# VoltageSourcePCB.net
KiCad netlist of a schematic drawn in EAGLE
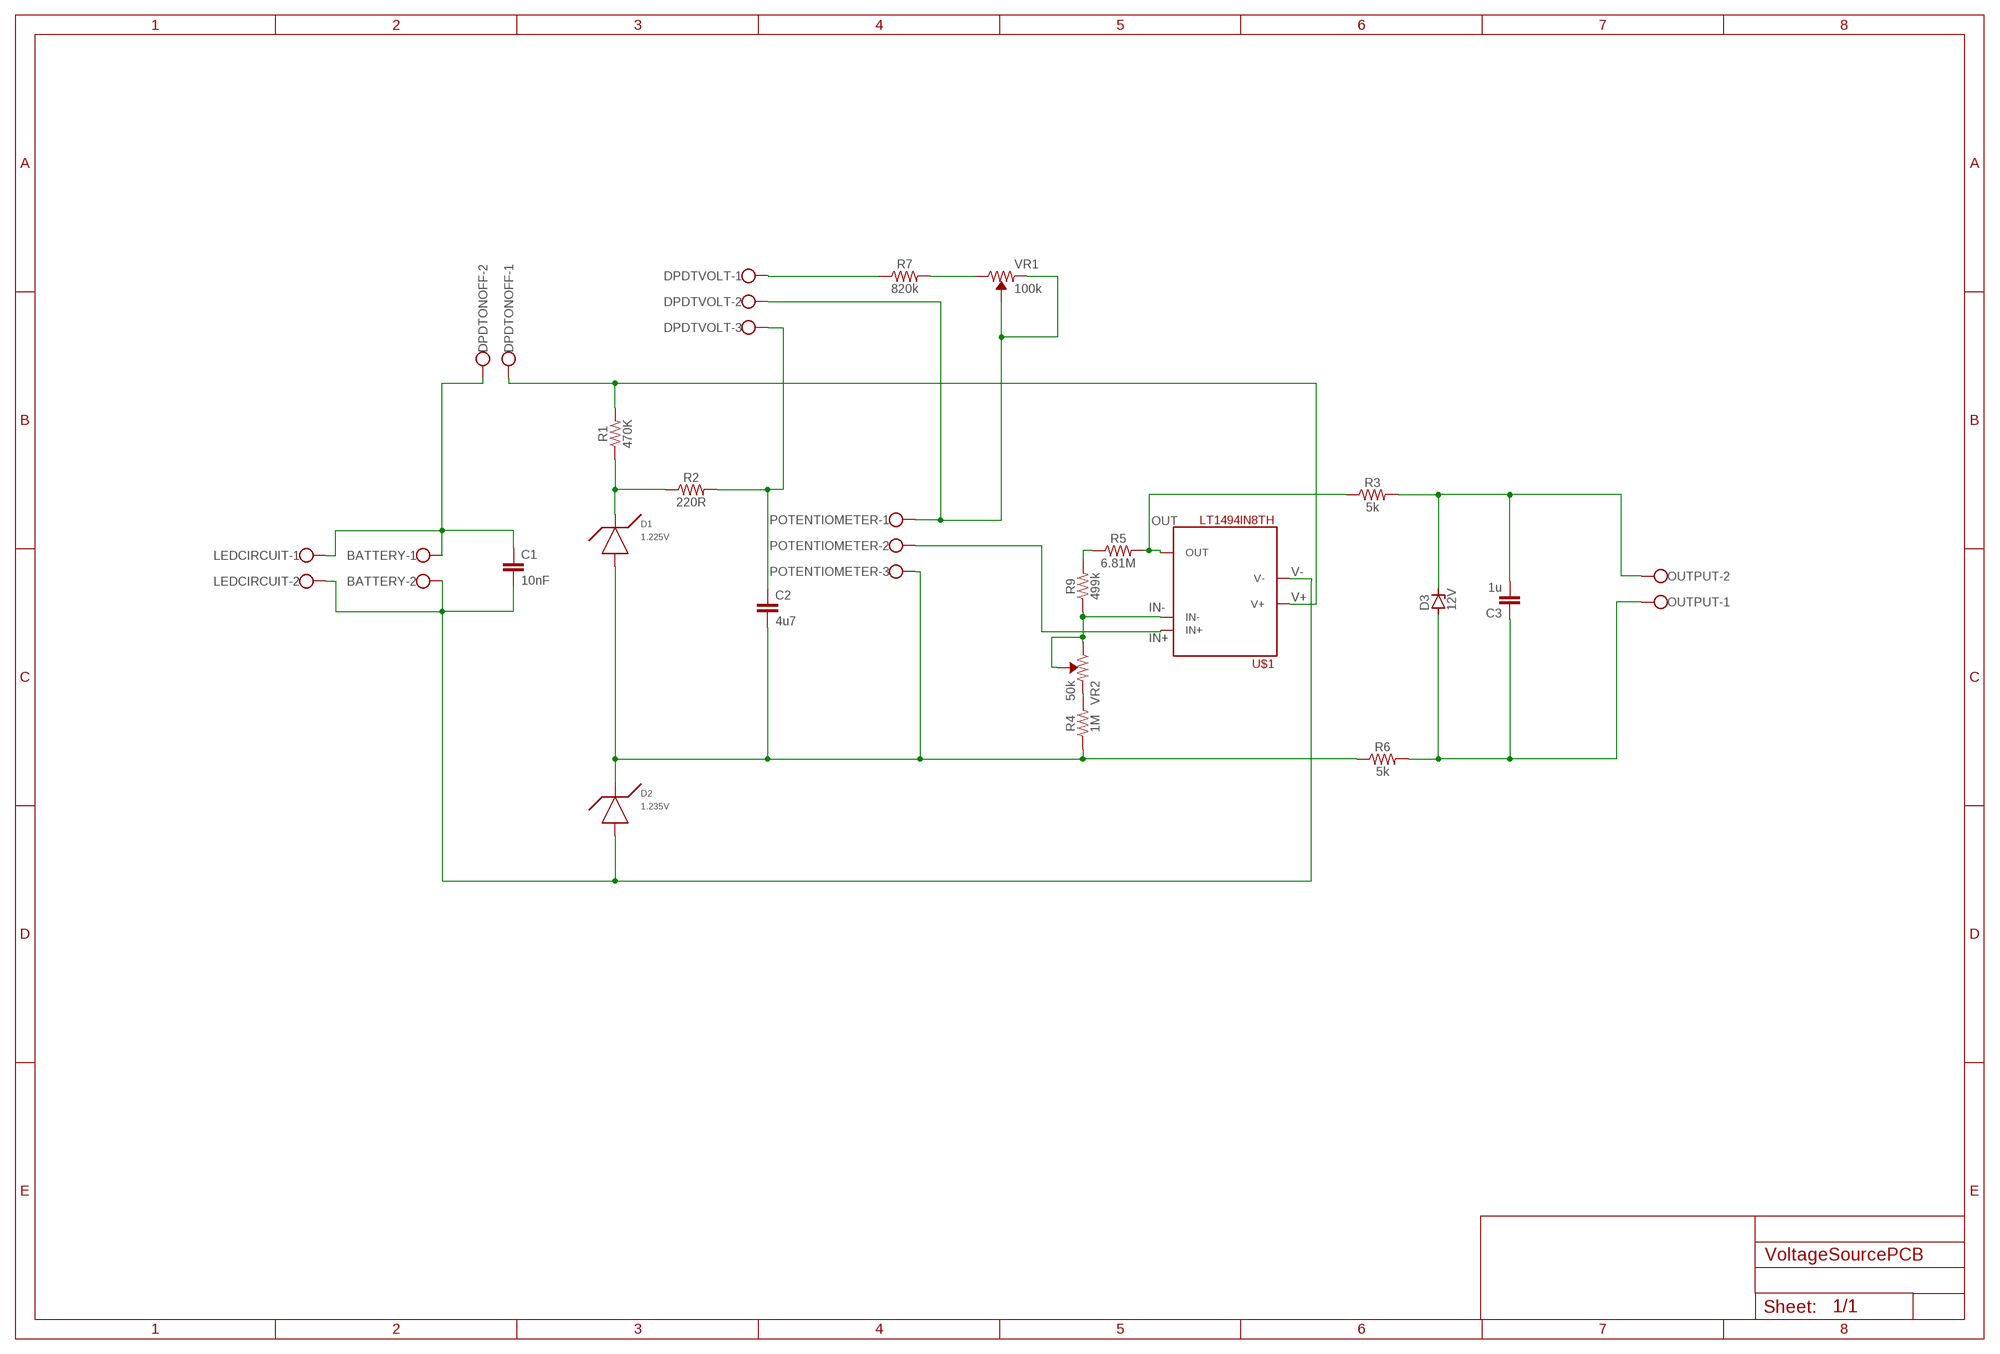
[diagram p0: schematic, sheet 1]

(export (version "E")
  (design (tool "Eeschema 10.0.6"))
  (components
    (comp (ref "BATTERY")
      (value "W237-102")
      (footprint "eagle-import:W237-102")
      (fields (field (name "MPN") "237-102"))
      (libsource (lib "eagle-import") (part "W237-102"))
    )
    (comp (ref "C1")
      (value "10nF")
      (footprint "eagle-import:C5B2.5")
      (libsource (lib "eagle-import") (part "C5/2.5"))
    )
    (comp (ref "C2")
      (value "4u7")
      (footprint "eagle-import:C22.5B11")
      (libsource (lib "eagle-import") (part "C22/11"))
    )
    (comp (ref "C3")
      (value "1u")
      (footprint "eagle-import:C150-072X183")
      (libsource (lib "eagle-import") (part "C-EU150-072X183"))
    )
    (comp (ref "D1")
      (value "1.225V")
      (footprint "eagle-import:LT1004CZ")
      (libsource (lib "eagle-import") (part "LT1004CZ1.225V"))
    )
    (comp (ref "D2")
      (value "1.235V")
      (footprint "eagle-import:LT1004CZ")
      (libsource (lib "eagle-import") (part "LT1004CZ1.235V"))
    )
    (comp (ref "D3")
      (value "12V")
      (footprint "eagle-import:C1702-15")
      (libsource (lib "eagle-import") (part "ZENER-DIODEC1702-15"))
    )
    (comp (ref "DPDTONOFF")
      (value "W237-102")
      (footprint "eagle-import:W237-102")
      (fields (field (name "MPN") "237-102"))
      (libsource (lib "eagle-import") (part "W237-102"))
    )
    (comp (ref "DPDTVOLT")
      (value "W237-103")
      (footprint "eagle-import:W237-103")
      (fields (field (name "MPN") "237-103"))
      (libsource (lib "eagle-import") (part "W237-103"))
    )
    (comp (ref "LEDCIRCUIT")
      (value "W237-102")
      (footprint "eagle-import:W237-102")
      (fields (field (name "MPN") "237-102"))
      (libsource (lib "eagle-import") (part "W237-102"))
    )
    (comp (ref "OUTPUT")
      (value "W237-102")
      (footprint "eagle-import:W237-102")
      (fields (field (name "MPN") "237-102"))
      (libsource (lib "eagle-import") (part "W237-102"))
    )
    (comp (ref "POTENTIOMETER")
      (value "W237-103")
      (footprint "eagle-import:W237-103")
      (fields (field (name "MPN") "237-103"))
      (libsource (lib "eagle-import") (part "W237-103"))
    )
    (comp (ref "R1")
      (value "470K")
      (footprint "eagle-import:0805")
      (libsource (lib "eagle-import") (part "RESISTOR0805"))
    )
    (comp (ref "R2")
      (value "220R")
      (footprint "eagle-import:0805")
      (libsource (lib "eagle-import") (part "RESISTOR0805"))
    )
    (comp (ref "R3")
      (value "5k")
      (footprint "eagle-import:0805")
      (libsource (lib "eagle-import") (part "RESISTOR0805"))
    )
    (comp (ref "R4")
      (value "1M")
      (footprint "eagle-import:0805")
      (libsource (lib "eagle-import") (part "RESISTOR0805"))
    )
    (comp (ref "R5")
      (value "6.81M")
      (footprint "eagle-import:0805")
      (libsource (lib "eagle-import") (part "RESISTOR0805"))
    )
    (comp (ref "R6")
      (value "5k")
      (footprint "eagle-import:0805")
      (libsource (lib "eagle-import") (part "RESISTOR0805"))
    )
    (comp (ref "R7")
      (value "820k")
      (footprint "eagle-import:0805")
      (libsource (lib "eagle-import") (part "RESISTOR0805"))
    )
    (comp (ref "R9")
      (value "499k")
      (footprint "eagle-import:0805")
      (libsource (lib "eagle-import") (part "RESISTOR0805"))
    )
    (comp (ref "U$1")
      (value "LT1494IN8TH")
      (footprint "eagle-import:LT1494TH")
      (libsource (lib "eagle-import") (part "LT1494IN8TH"))
    )
    (comp (ref "VR1")
      (value "100k")
      (footprint "eagle-import:TRIMPOT-SMD-TC33X")
      (libsource (lib "eagle-import") (part "TRIMPOT-SMD-3MM-OPEN-1/10W-25%"))
    )
    (comp (ref "VR2")
      (value "50k")
      (footprint "eagle-import:TRIMPOT-SMD-TC33X")
      (libsource (lib "eagle-import") (part "TRIMPOT-SMD-3MM-OPEN-1/10W-25%"))
    )
  )
  (nets
    (net (code "1") (name "/IN+") (class "Default")
      (node (ref "POTENTIOMETER") (pin "2") (pinfunction "KL_2") (pintype "passive"))
      (node (ref "U$1") (pin "3") (pinfunction "IN+_3") (pintype "input"))
    )
    (net (code "2") (name "/IN-") (class "Default")
      (node (ref "R9") (pin "1") (pinfunction "1_1") (pintype "passive"))
      (node (ref "U$1") (pin "2") (pinfunction "IN-_2") (pintype "input"))
      (node (ref "VR2") (pin "1") (pinfunction "CW_1") (pintype "passive"))
      (node (ref "VR2") (pin "2") (pinfunction "WIPER_2") (pintype "passive"))
    )
    (net (code "3") (name "/OUT") (class "Default")
      (node (ref "R3") (pin "1") (pinfunction "1_1") (pintype "passive"))
      (node (ref "R5") (pin "2") (pinfunction "2_2") (pintype "passive"))
      (node (ref "U$1") (pin "6") (pinfunction "OUT_6") (pintype "output"))
    )
    (net (code "4") (name "/V+") (class "Default")
      (node (ref "DPDTONOFF") (pin "1") (pinfunction "KL_1") (pintype "passive"))
      (node (ref "R1") (pin "2") (pinfunction "2_2") (pintype "passive"))
      (node (ref "U$1") (pin "7") (pinfunction "V+_7") (pintype "power_in"))
    )
    (net (code "5") (name "/V-") (class "Default")
      (node (ref "BATTERY") (pin "2") (pinfunction "KL_2") (pintype "passive"))
      (node (ref "C1") (pin "2") (pinfunction "2_2") (pintype "passive"))
      (node (ref "D2") (pin "ANODE") (pinfunction "ANODE_ANODE") (pintype "bidirectional"))
      (node (ref "LEDCIRCUIT") (pin "2") (pinfunction "KL_2") (pintype "passive"))
      (node (ref "U$1") (pin "4") (pinfunction "V-_4") (pintype "power_in"))
    )
    (net (code "6") (name "Net-(BATTERYA-KL)") (class "Default")
      (node (ref "BATTERY") (pin "1") (pinfunction "KL_1") (pintype "passive"))
      (node (ref "C1") (pin "1") (pinfunction "1_1") (pintype "passive"))
      (node (ref "DPDTONOFF") (pin "2") (pinfunction "KL_2") (pintype "passive"))
      (node (ref "LEDCIRCUIT") (pin "1") (pinfunction "KL_1") (pintype "passive"))
    )
    (net (code "7") (name "Net-(D1-PadCATHODE)") (class "Default")
      (node (ref "D1") (pin "CATHODE") (pinfunction "CATHODE_CATHODE") (pintype "bidirectional"))
      (node (ref "R1") (pin "1") (pinfunction "1_1") (pintype "passive"))
      (node (ref "R2") (pin "1") (pinfunction "1_1") (pintype "passive"))
    )
    (net (code "8") (name "Net-(DPDTVOLTA-KL)") (class "Default")
      (node (ref "DPDTVOLT") (pin "1") (pinfunction "KL_1") (pintype "passive"))
      (node (ref "R7") (pin "1") (pinfunction "1_1") (pintype "passive"))
    )
    (net (code "9") (name "Net-(DPDTVOLTB-KL)") (class "Default")
      (node (ref "DPDTVOLT") (pin "2") (pinfunction "KL_2") (pintype "passive"))
      (node (ref "POTENTIOMETER") (pin "1") (pinfunction "KL_1") (pintype "passive"))
      (node (ref "VR1") (pin "2") (pinfunction "WIPER_2") (pintype "passive"))
      (node (ref "VR1") (pin "3") (pinfunction "CCW_3") (pintype "passive"))
    )
    (net (code "10") (name "Net-(DPDTVOLTC-KL)") (class "Default")
      (node (ref "C2") (pin "1") (pinfunction "1_1") (pintype "passive"))
      (node (ref "DPDTVOLT") (pin "3") (pinfunction "KL_3") (pintype "passive"))
      (node (ref "R2") (pin "2") (pinfunction "2_2") (pintype "passive"))
    )
    (net (code "11") (name "Net-(OUTPUTA-KL)") (class "Default")
      (node (ref "C3") (pin "1") (pinfunction "1_1") (pintype "passive"))
      (node (ref "D3") (pin "A") (pinfunction "A_A") (pintype "passive"))
      (node (ref "OUTPUT") (pin "1") (pinfunction "KL_1") (pintype "passive"))
      (node (ref "R6") (pin "2") (pinfunction "2_2") (pintype "passive"))
    )
    (net (code "12") (name "Net-(OUTPUTB-KL)") (class "Default")
      (node (ref "C3") (pin "2") (pinfunction "2_2") (pintype "passive"))
      (node (ref "D3") (pin "C") (pinfunction "C_C") (pintype "passive"))
      (node (ref "OUTPUT") (pin "2") (pinfunction "KL_2") (pintype "passive"))
      (node (ref "R3") (pin "2") (pinfunction "2_2") (pintype "passive"))
    )
    (net (code "13") (name "Net-(POTENTIOMETERC-KL)") (class "Default")
      (node (ref "C2") (pin "2") (pinfunction "2_2") (pintype "passive"))
      (node (ref "D1") (pin "ANODE") (pinfunction "ANODE_ANODE") (pintype "bidirectional"))
      (node (ref "D2") (pin "CATHODE") (pinfunction "CATHODE_CATHODE") (pintype "bidirectional"))
      (node (ref "POTENTIOMETER") (pin "3") (pinfunction "KL_3") (pintype "passive"))
      (node (ref "R4") (pin "1") (pinfunction "1_1") (pintype "passive"))
      (node (ref "R6") (pin "1") (pinfunction "1_1") (pintype "passive"))
    )
    (net (code "14") (name "Net-(R5-Pad1)") (class "Default")
      (node (ref "R5") (pin "1") (pinfunction "1_1") (pintype "passive"))
      (node (ref "R9") (pin "2") (pinfunction "2_2") (pintype "passive"))
    )
    (net (code "15") (name "Net-(VR1-CW)") (class "Default")
      (node (ref "R7") (pin "2") (pinfunction "2_2") (pintype "passive"))
      (node (ref "VR1") (pin "1") (pinfunction "CW_1") (pintype "passive"))
    )
    (net (code "16") (name "Net-(VR2-CCW)") (class "Default")
      (node (ref "R4") (pin "2") (pinfunction "2_2") (pintype "passive"))
      (node (ref "VR2") (pin "3") (pinfunction "CCW_3") (pintype "passive"))
    )
  )
)
